# 12_LED.net
KiCad netlist of a schematic drawn in Altium Designer
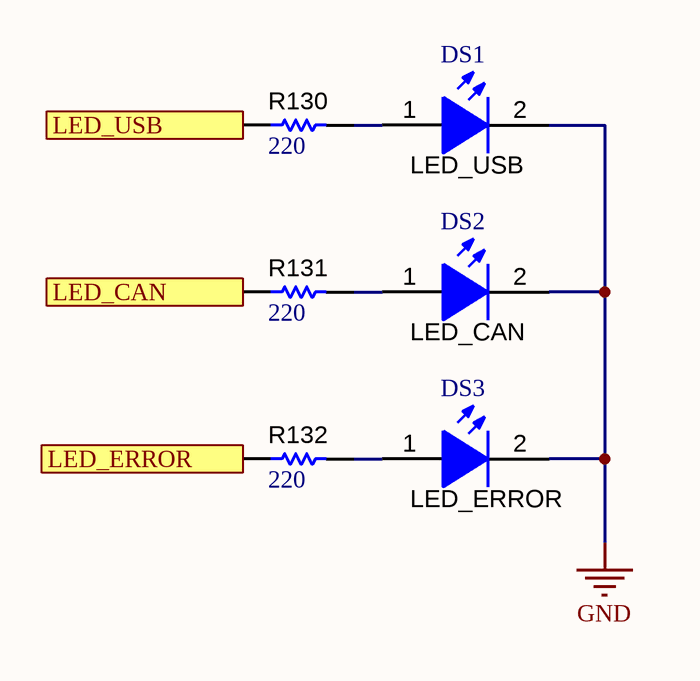
[diagram p0: 12_LED.SchDoc]

(export (version "E")
  (design (tool "Eeschema 10.0.6"))
  (components
    (comp (ref "DS1")
      (value "LED_USB")
      (footprint "LS L29K_Red")
      (description "LED, Red, SMD")
      (fields (field (name "MANUFACTURER") "OSRAM") (field (name "PARTNUMBER") "LS L29K-G1J2-1-Z"))
      (libsource (lib "PROC051C_AWR1843BOOST_RevC") (part "LED RED SMD"))
    )
    (comp (ref "DS2")
      (value "LED_CAN")
      (footprint "LS L29K_Red")
      (description "LED, Red, SMD")
      (fields (field (name "MANUFACTURER") "OSRAM") (field (name "PARTNUMBER") "LS L29K-G1J2-1-Z"))
      (libsource (lib "PROC051C_AWR1843BOOST_RevC") (part "LED RED SMD"))
    )
    (comp (ref "DS3")
      (value "LED_ERROR")
      (footprint "LS L29K_Red")
      (description "LED, Red, SMD")
      (fields (field (name "MANUFACTURER") "OSRAM") (field (name "PARTNUMBER") "LS L29K-G1J2-1-Z"))
      (libsource (lib "PROC051C_AWR1843BOOST_RevC") (part "LED RED SMD"))
    )
    (comp (ref "R130")
      (value "CRCW04021K00FKED")
      (footprint "0402L")
      (description "RES, 1.00 k, 1%, 0.063 W, AEC-Q200 Grade 0, 0402")
      (fields (field (name "MANUFACTURER") "Vishay-Dale") (field (name "VALUEDISPLAYED") "220"))
      (libsource (lib "PROC051C_AWR1843BOOST_RevC") (part "RES 1K 0402"))
    )
    (comp (ref "R131")
      (value "CRCW04021K00FKED")
      (footprint "0402L")
      (description "RES, 1.00 k, 1%, 0.063 W, AEC-Q200 Grade 0, 0402")
      (fields (field (name "MANUFACTURER") "Vishay-Dale") (field (name "VALUEDISPLAYED") "220"))
      (libsource (lib "PROC051C_AWR1843BOOST_RevC") (part "RES 1K 0402"))
    )
    (comp (ref "R132")
      (value "CRCW04021K00FKED")
      (footprint "0402L")
      (description "RES, 1.00 k, 1%, 0.063 W, AEC-Q200 Grade 0, 0402")
      (fields (field (name "MANUFACTURER") "Vishay-Dale") (field (name "VALUEDISPLAYED") "220"))
      (libsource (lib "PROC051C_AWR1843BOOST_RevC") (part "RES 1K 0402"))
    )
  )
  (nets
    (net (code "1") (name "/LED_CAN") (class "Default")
      (node (ref "R131") (pin "1") (pinfunction "1_1") (pintype "passive"))
    )
    (net (code "2") (name "/LED_ERROR") (class "Default")
      (node (ref "R132") (pin "1") (pinfunction "1_1") (pintype "passive"))
    )
    (net (code "3") (name "/LED_USB") (class "Default")
      (node (ref "R130") (pin "1") (pinfunction "1_1") (pintype "passive"))
    )
    (net (code "4") (name "GND") (class "Default")
      (node (ref "DS1") (pin "2") (pinfunction "K_2") (pintype "passive"))
      (node (ref "DS2") (pin "2") (pinfunction "K_2") (pintype "passive"))
      (node (ref "DS3") (pin "2") (pinfunction "K_2") (pintype "passive"))
    )
    (net (code "5") (name "Net-(DS1-A)") (class "Default")
      (node (ref "DS1") (pin "1") (pinfunction "A_1") (pintype "passive"))
      (node (ref "R130") (pin "2") (pinfunction "2_2") (pintype "passive"))
    )
    (net (code "6") (name "Net-(DS2-A)") (class "Default")
      (node (ref "DS2") (pin "1") (pinfunction "A_1") (pintype "passive"))
      (node (ref "R131") (pin "2") (pinfunction "2_2") (pintype "passive"))
    )
    (net (code "7") (name "Net-(DS3-A)") (class "Default")
      (node (ref "DS3") (pin "1") (pinfunction "A_1") (pintype "passive"))
      (node (ref "R132") (pin "2") (pinfunction "2_2") (pintype "passive"))
    )
  )
)
